# PCIE.net
KiCad netlist of a schematic drawn in Altium Designer
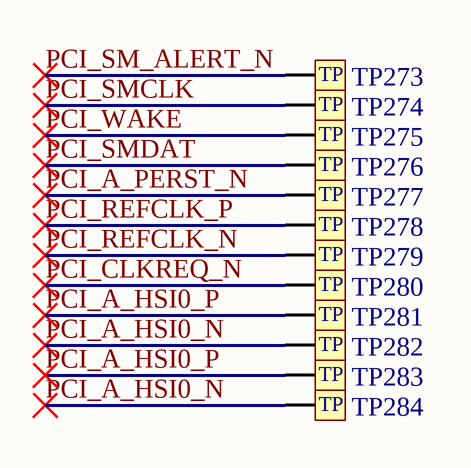
[diagram p0: PCIE.SchDoc]

(export (version "E")
  (design (tool "Eeschema 10.0.6"))
  (components
    (comp (ref "TP273")
      (value "TP_0P8MM")
      (footprint "TP_0P8MM")
      (description "OSM Footprint 0P8 LGA Ball")
      (libsource (lib "Jumper") (part "TP_0P8MM"))
    )
    (comp (ref "TP274")
      (value "TP_0P8MM")
      (footprint "TP_0P8MM")
      (description "OSM Footprint 0P8 LGA Ball")
      (libsource (lib "Jumper") (part "TP_0P8MM"))
    )
    (comp (ref "TP275")
      (value "TP_0P8MM")
      (footprint "TP_0P8MM")
      (description "OSM Footprint 0P8 LGA Ball")
      (libsource (lib "Jumper") (part "TP_0P8MM"))
    )
    (comp (ref "TP276")
      (value "TP_0P8MM")
      (footprint "TP_0P8MM")
      (description "OSM Footprint 0P8 LGA Ball")
      (libsource (lib "Jumper") (part "TP_0P8MM"))
    )
    (comp (ref "TP277")
      (value "TP_0P8MM")
      (footprint "TP_0P8MM")
      (description "OSM Footprint 0P8 LGA Ball")
      (libsource (lib "Jumper") (part "TP_0P8MM"))
    )
    (comp (ref "TP278")
      (value "TP_0P8MM")
      (footprint "TP_0P8MM")
      (description "OSM Footprint 0P8 LGA Ball")
      (libsource (lib "Jumper") (part "TP_0P8MM"))
    )
    (comp (ref "TP279")
      (value "TP_0P8MM")
      (footprint "TP_0P8MM")
      (description "OSM Footprint 0P8 LGA Ball")
      (libsource (lib "Jumper") (part "TP_0P8MM"))
    )
    (comp (ref "TP280")
      (value "TP_0P8MM")
      (footprint "TP_0P8MM")
      (description "OSM Footprint 0P8 LGA Ball")
      (libsource (lib "Jumper") (part "TP_0P8MM"))
    )
    (comp (ref "TP281")
      (value "TP_0P8MM")
      (footprint "TP_0P8MM")
      (description "OSM Footprint 0P8 LGA Ball")
      (libsource (lib "Jumper") (part "TP_0P8MM"))
    )
    (comp (ref "TP282")
      (value "TP_0P8MM")
      (footprint "TP_0P8MM")
      (description "OSM Footprint 0P8 LGA Ball")
      (libsource (lib "Jumper") (part "TP_0P8MM"))
    )
    (comp (ref "TP283")
      (value "TP_0P8MM")
      (footprint "TP_0P8MM")
      (description "OSM Footprint 0P8 LGA Ball")
      (libsource (lib "Jumper") (part "TP_0P8MM"))
    )
    (comp (ref "TP284")
      (value "TP_0P8MM")
      (footprint "TP_0P8MM")
      (description "OSM Footprint 0P8 LGA Ball")
      (libsource (lib "Jumper") (part "TP_0P8MM"))
    )
  )
  (nets
    (net (code "1") (name "/PCI_A_HSI0_N") (class "Default")
      (node (ref "TP282") (pin "1") (pinfunction "1_1") (pintype "passive"))
      (node (ref "TP284") (pin "1") (pinfunction "1_1") (pintype "passive"))
    )
    (net (code "2") (name "/PCI_A_HSI0_P") (class "Default")
      (node (ref "TP281") (pin "1") (pinfunction "1_1") (pintype "passive"))
      (node (ref "TP283") (pin "1") (pinfunction "1_1") (pintype "passive"))
    )
    (net (code "3") (name "/PCI_A_PERST_N") (class "Default")
      (node (ref "TP277") (pin "1") (pinfunction "1_1") (pintype "passive+no_connect"))
    )
    (net (code "4") (name "/PCI_CLKREQ_N") (class "Default")
      (node (ref "TP280") (pin "1") (pinfunction "1_1") (pintype "passive+no_connect"))
    )
    (net (code "5") (name "/PCI_REFCLK_N") (class "Default")
      (node (ref "TP279") (pin "1") (pinfunction "1_1") (pintype "passive+no_connect"))
    )
    (net (code "6") (name "/PCI_REFCLK_P") (class "Default")
      (node (ref "TP278") (pin "1") (pinfunction "1_1") (pintype "passive+no_connect"))
    )
    (net (code "7") (name "/PCI_SMCLK") (class "Default")
      (node (ref "TP274") (pin "1") (pinfunction "1_1") (pintype "passive+no_connect"))
    )
    (net (code "8") (name "/PCI_SMDAT") (class "Default")
      (node (ref "TP276") (pin "1") (pinfunction "1_1") (pintype "passive+no_connect"))
    )
    (net (code "9") (name "/PCI_SM_ALERT_N") (class "Default")
      (node (ref "TP273") (pin "1") (pinfunction "1_1") (pintype "passive+no_connect"))
    )
    (net (code "10") (name "/PCI_WAKE") (class "Default")
      (node (ref "TP275") (pin "1") (pinfunction "1_1") (pintype "passive+no_connect"))
    )
  )
)
